# Schematic.net
KiCad netlist of a schematic drawn in Altium Designer
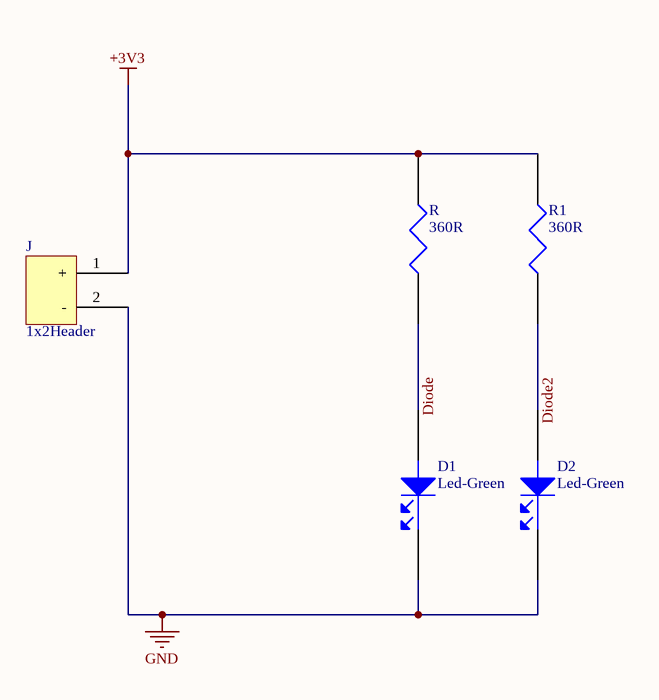
[diagram p0: Schematic.SchDoc]

(export (version "E")
  (design (tool "Eeschema 10.0.6"))
  (components
    (comp (ref "D1")
      (value "Led-Green")
      (footprint "LED0603G")
      (description "Single Color LED, Green, Water Clear, 1.1mm")
      (fields
        (field (name "MANUFACTURER") "Wurth Electronics")
        (field (name "MANUFACTURER PART NUMBER") "150060GS75000")
      )
      (libsource (lib "Sch_lib") (part "150060GS75000"))
    )
    (comp (ref "D2")
      (value "Led-Green")
      (footprint "LED0603G")
      (description "Single Color LED, Green, Water Clear, 1.1mm")
      (fields
        (field (name "MANUFACTURER") "Wurth Electronics")
        (field (name "MANUFACTURER PART NUMBER") "150060GS75000")
      )
      (libsource (lib "Sch_lib") (part "150060GS75000"))
    )
    (comp (ref "J")
      (value "1x2Header")
      (footprint "HDR1X2")
      (fields (field (name "MANUFACTURER") "Molex") (field (name "MANUFACTURER PART NUMBER") "22-29-2021"))
      (libsource (lib "Sch_lib") (part "22-29-2021"))
    )
    (comp (ref "R")
      (value "360R")
      (footprint "R805")
      (fields
        (field (name "MANUFACTURER") "Yageo")
        (field (name "MANUFACTURER PART NUMBER") "RC0805JR-07360RL")
        (field (name "TOLERANCE") "5%")
      )
      (libsource (lib "Sch_lib") (part "RC0805JR-07360RL"))
    )
    (comp (ref "R1")
      (value "360R")
      (footprint "R805")
      (fields
        (field (name "MANUFACTURER") "Yageo")
        (field (name "MANUFACTURER PART NUMBER") "RC0805JR-07360RL")
        (field (name "TOLERANCE") "5%")
      )
      (libsource (lib "Sch_lib") (part "RC0805JR-07360RL"))
    )
  )
  (nets
    (net (code "1") (name "+3V3") (class "Default")
      (node (ref "J") (pin "1") (pinfunction "+_1") (pintype "passive"))
      (node (ref "R") (pin "2") (pinfunction "2_2") (pintype "passive"))
      (node (ref "R1") (pin "2") (pinfunction "2_2") (pintype "passive"))
    )
    (net (code "2") (name "/Diode") (class "Default")
      (node (ref "D1") (pin "1") (pinfunction "1_1") (pintype "passive"))
      (node (ref "R") (pin "1") (pinfunction "1_1") (pintype "passive"))
    )
    (net (code "3") (name "/Diode2") (class "Default")
      (node (ref "D2") (pin "1") (pinfunction "1_1") (pintype "passive"))
      (node (ref "R1") (pin "1") (pinfunction "1_1") (pintype "passive"))
    )
    (net (code "4") (name "GND") (class "Default")
      (node (ref "D1") (pin "2") (pinfunction "2_2") (pintype "passive"))
      (node (ref "D2") (pin "2") (pinfunction "2_2") (pintype "passive"))
      (node (ref "J") (pin "2") (pinfunction "-_2") (pintype "passive"))
    )
  )
)
